# ESP32C3_VOICE_LED_ES7243E_Sheet.net
KiCad netlist of a schematic drawn in Altium Designer
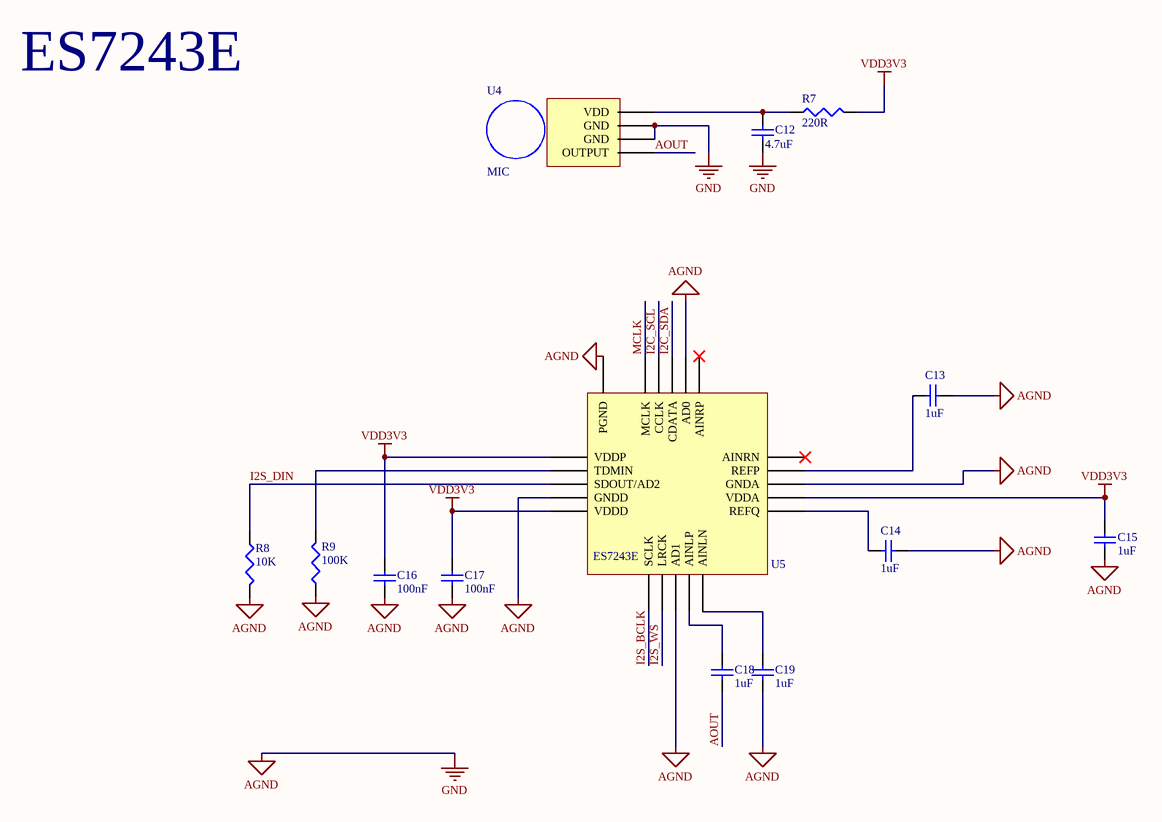
[diagram p0: ESP32C3_VOICE_LED_ES7243E_Sheet.SchDoc]

(export (version "E")
  (design (tool "Eeschema 10.0.6"))
  (components
    (comp (ref "C12")
      (value "4.7uF")
      (footprint "0603")
      (description "Capacitor")
      (fields (field (name "Comment") "Cap") (field (name "PUBLISHER") "Altium Limited"))
      (libsource (lib "CORE_COMPONENT") (part "Cap"))
    )
    (comp (ref "C13")
      (value "1uF")
      (footprint "0603")
      (description "Capacitor")
      (fields (field (name "Comment") "Cap") (field (name "PUBLISHER") "Altium Limited"))
      (libsource (lib "CORE_COMPONENT") (part "Cap"))
    )
    (comp (ref "C14")
      (value "1uF")
      (footprint "0603")
      (description "Capacitor")
      (fields (field (name "Comment") "Cap") (field (name "PUBLISHER") "Altium Limited"))
      (libsource (lib "CORE_COMPONENT") (part "Cap"))
    )
    (comp (ref "C15")
      (value "1uF")
      (footprint "0603")
      (description "Capacitor")
      (fields (field (name "Comment") "Cap") (field (name "PUBLISHER") "Altium Limited"))
      (libsource (lib "CORE_COMPONENT") (part "Cap"))
    )
    (comp (ref "C16")
      (value "100nF")
      (footprint "0603")
      (description "Capacitor")
      (fields (field (name "Comment") "Cap") (field (name "PUBLISHER") "Altium Limited"))
      (libsource (lib "CORE_COMPONENT") (part "Cap"))
    )
    (comp (ref "C17")
      (value "100nF")
      (footprint "0603")
      (description "Capacitor")
      (fields (field (name "Comment") "Cap") (field (name "PUBLISHER") "Altium Limited"))
      (libsource (lib "CORE_COMPONENT") (part "Cap"))
    )
    (comp (ref "C18")
      (value "1uF")
      (footprint "0603")
      (description "Capacitor")
      (fields (field (name "Comment") "Cap") (field (name "PUBLISHER") "Altium Limited"))
      (libsource (lib "CORE_COMPONENT") (part "Cap"))
    )
    (comp (ref "C19")
      (value "1uF")
      (footprint "0603")
      (description "Capacitor")
      (fields (field (name "Comment") "Cap") (field (name "PUBLISHER") "Altium Limited"))
      (libsource (lib "CORE_COMPONENT") (part "Cap"))
    )
    (comp (ref "R7")
      (value "220R")
      (footprint "0603")
      (description "Resistor")
      (fields (field (name "Comment") "Res") (field (name "PUBLISHER") "Altium Limited"))
      (libsource (lib "CORE_COMPONENT") (part "Res"))
    )
    (comp (ref "R8")
      (value "10K")
      (footprint "0603")
      (description "Resistor")
      (fields (field (name "Comment") "Res") (field (name "PUBLISHER") "Altium Limited"))
      (libsource (lib "CORE_COMPONENT") (part "Res"))
    )
    (comp (ref "R9")
      (value "100K")
      (footprint "0603")
      (description "Resistor")
      (fields (field (name "Comment") "Res") (field (name "PUBLISHER") "Altium Limited"))
      (libsource (lib "CORE_COMPONENT") (part "Res"))
    )
    (comp (ref "U4")
      (value "MIC")
      (footprint "MIC_XHXDZ_2718")
      (libsource (lib "CORE_COMPONENT") (part "MIC_XHXDZ_2718"))
    )
    (comp (ref "U5")
      (value "ES7243E")
      (footprint "QFN20_3X3")
      (libsource (lib "CORE_COMPONENT") (part "ES7243E"))
    )
  )
  (nets
    (net (code "1") (name "/AOUT") (class "Default")
      (node (ref "C18") (pin "1") (pinfunction "1_1") (pintype "passive"))
      (node (ref "U4") (pin "4") (pinfunction "OUTPUT_4") (pintype "passive"))
    )
    (net (code "2") (name "/I2C_SCL") (class "Default")
      (node (ref "U5") (pin "19") (pinfunction "CCLK_19") (pintype "passive"))
    )
    (net (code "3") (name "/I2C_SDA") (class "Default")
      (node (ref "U5") (pin "18") (pinfunction "CDATA_18") (pintype "passive"))
    )
    (net (code "4") (name "/I2S_BCLK") (class "Default")
      (node (ref "U5") (pin "6") (pinfunction "SCLK_6") (pintype "passive"))
    )
    (net (code "5") (name "/I2S_DIN") (class "Default")
      (node (ref "R8") (pin "1") (pinfunction "1_1") (pintype "passive"))
      (node (ref "U5") (pin "3") (pinfunction "SDOUT/AD2_3") (pintype "passive"))
    )
    (net (code "6") (name "/I2S_WS") (class "Default")
      (node (ref "U5") (pin "7") (pinfunction "LRCK_7") (pintype "passive"))
    )
    (net (code "7") (name "/MCLK") (class "Default")
      (node (ref "U5") (pin "20") (pinfunction "MCLK_20") (pintype "passive"))
    )
    (net (code "8") (name "AGND") (class "Default")
      (node (ref "C12") (pin "1") (pinfunction "1_1") (pintype "passive"))
      (node (ref "C13") (pin "2") (pinfunction "2_2") (pintype "passive"))
      (node (ref "C14") (pin "2") (pinfunction "2_2") (pintype "passive"))
      (node (ref "C15") (pin "2") (pinfunction "2_2") (pintype "passive"))
      (node (ref "C16") (pin "1") (pinfunction "1_1") (pintype "passive"))
      (node (ref "C17") (pin "1") (pinfunction "1_1") (pintype "passive"))
      (node (ref "C19") (pin "1") (pinfunction "1_1") (pintype "passive"))
      (node (ref "R8") (pin "2") (pinfunction "2_2") (pintype "passive"))
      (node (ref "R9") (pin "1") (pinfunction "1_1") (pintype "passive"))
      (node (ref "U4") (pin "2") (pinfunction "GND_2") (pintype "passive"))
      (node (ref "U4") (pin "3") (pinfunction "GND_3") (pintype "passive"))
      (node (ref "U5") (pin "13") (pinfunction "GNDA_13") (pintype "passive"))
      (node (ref "U5") (pin "17") (pinfunction "AD0_17") (pintype "passive"))
      (node (ref "U5") (pin "21") (pinfunction "PGND_21") (pintype "passive"))
      (node (ref "U5") (pin "4") (pinfunction "GNDD_4") (pintype "passive"))
      (node (ref "U5") (pin "8") (pinfunction "AD1_8") (pintype "passive"))
    )
    (net (code "9") (name "Net-(U4-VDD)") (class "Default")
      (node (ref "C12") (pin "2") (pinfunction "2_2") (pintype "passive"))
      (node (ref "R7") (pin "1") (pinfunction "1_1") (pintype "passive"))
      (node (ref "U4") (pin "1") (pinfunction "VDD_1") (pintype "passive"))
    )
    (net (code "10") (name "Net-(U5-AINLN)") (class "Default")
      (node (ref "C19") (pin "2") (pinfunction "2_2") (pintype "passive"))
      (node (ref "U5") (pin "10") (pinfunction "AINLN_10") (pintype "passive"))
    )
    (net (code "11") (name "Net-(U5-AINLP)") (class "Default")
      (node (ref "C18") (pin "2") (pinfunction "2_2") (pintype "passive"))
      (node (ref "U5") (pin "9") (pinfunction "AINLP_9") (pintype "passive"))
    )
    (net (code "12") (name "Net-(U5-REFP)") (class "Default")
      (node (ref "C13") (pin "1") (pinfunction "1_1") (pintype "passive"))
      (node (ref "U5") (pin "14") (pinfunction "REFP_14") (pintype "passive"))
    )
    (net (code "13") (name "Net-(U5-REFQ)") (class "Default")
      (node (ref "C14") (pin "1") (pinfunction "1_1") (pintype "passive"))
      (node (ref "U5") (pin "11") (pinfunction "REFQ_11") (pintype "passive"))
    )
    (net (code "14") (name "Net-(U5-TDMIN)") (class "Default")
      (node (ref "R9") (pin "2") (pinfunction "2_2") (pintype "passive"))
      (node (ref "U5") (pin "2") (pinfunction "TDMIN_2") (pintype "passive"))
    )
    (net (code "15") (name "VDD3V3") (class "Default")
      (node (ref "C15") (pin "1") (pinfunction "1_1") (pintype "passive"))
      (node (ref "C16") (pin "2") (pinfunction "2_2") (pintype "passive"))
      (node (ref "C17") (pin "2") (pinfunction "2_2") (pintype "passive"))
      (node (ref "R7") (pin "2") (pinfunction "2_2") (pintype "passive"))
      (node (ref "U5") (pin "1") (pinfunction "VDDP_1") (pintype "passive"))
      (node (ref "U5") (pin "12") (pinfunction "VDDA_12") (pintype "passive"))
      (node (ref "U5") (pin "5") (pinfunction "VDDD_5") (pintype "passive"))
    )
    (net (code "16") (name "unconnected-(U5-AINRN-Pad15)") (class "Default")
      (node (ref "U5") (pin "15") (pinfunction "AINRN_15") (pintype "passive+no_connect"))
    )
    (net (code "17") (name "unconnected-(U5-AINRP-Pad16)") (class "Default")
      (node (ref "U5") (pin "16") (pinfunction "AINRP_16") (pintype "passive+no_connect"))
    )
  )
)
